# 16-BitSWStatusLed.net
KiCad netlist of a schematic drawn in Altium Designer
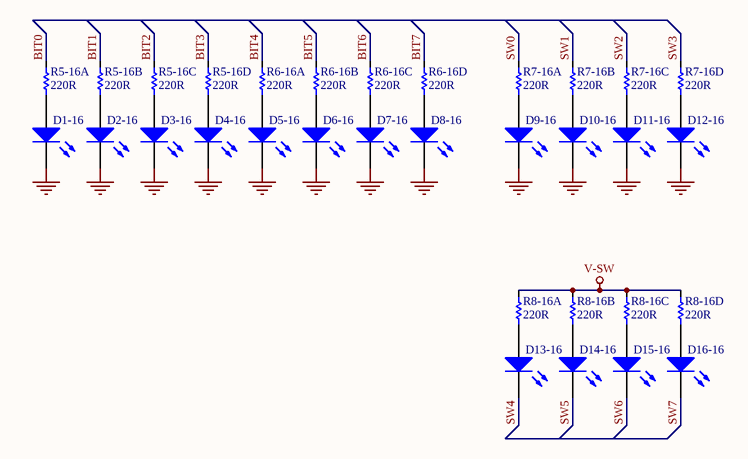
[diagram p0: 16-BitSWStatusLed.SchDoc]

(export (version "E")
  (design (tool "Eeschema 10.0.6"))
  (components
    (comp (ref "D1-16")
      (value "LED")
      (footprint "LED-0805")
      (description "Typical RED, GREEN, YELLOW, AMBER GaAs LED")
      (fields (field (name "PUBLISHER") "Altium Limited"))
      (libsource (lib "Miscellaneous Devices") (part "LED2"))
    )
    (comp (ref "D2-16")
      (value "LED")
      (footprint "LED-0805")
      (description "Typical RED, GREEN, YELLOW, AMBER GaAs LED")
      (fields (field (name "PUBLISHER") "Altium Limited"))
      (libsource (lib "Miscellaneous Devices") (part "LED2"))
    )
    (comp (ref "D3-16")
      (value "LED")
      (footprint "LED-0805")
      (description "Typical RED, GREEN, YELLOW, AMBER GaAs LED")
      (fields (field (name "PUBLISHER") "Altium Limited"))
      (libsource (lib "Miscellaneous Devices") (part "LED2"))
    )
    (comp (ref "D4-16")
      (value "LED")
      (footprint "LED-0805")
      (description "Typical RED, GREEN, YELLOW, AMBER GaAs LED")
      (fields (field (name "PUBLISHER") "Altium Limited"))
      (libsource (lib "Miscellaneous Devices") (part "LED2"))
    )
    (comp (ref "D5-16")
      (value "LED")
      (footprint "LED-0805")
      (description "Typical RED, GREEN, YELLOW, AMBER GaAs LED")
      (fields (field (name "PUBLISHER") "Altium Limited"))
      (libsource (lib "Miscellaneous Devices") (part "LED2"))
    )
    (comp (ref "D6-16")
      (value "LED")
      (footprint "LED-0805")
      (description "Typical RED, GREEN, YELLOW, AMBER GaAs LED")
      (fields (field (name "PUBLISHER") "Altium Limited"))
      (libsource (lib "Miscellaneous Devices") (part "LED2"))
    )
    (comp (ref "D7-16")
      (value "LED")
      (footprint "LED-0805")
      (description "Typical RED, GREEN, YELLOW, AMBER GaAs LED")
      (fields (field (name "PUBLISHER") "Altium Limited"))
      (libsource (lib "Miscellaneous Devices") (part "LED2"))
    )
    (comp (ref "D8-16")
      (value "LED")
      (footprint "LED-0805")
      (description "Typical RED, GREEN, YELLOW, AMBER GaAs LED")
      (fields (field (name "PUBLISHER") "Altium Limited"))
      (libsource (lib "Miscellaneous Devices") (part "LED2"))
    )
    (comp (ref "D9-16")
      (value "LED")
      (footprint "LED-0805")
      (description "Typical RED, GREEN, YELLOW, AMBER GaAs LED")
      (fields (field (name "PUBLISHER") "Altium Limited"))
      (libsource (lib "Miscellaneous Devices") (part "LED2"))
    )
    (comp (ref "D10-16")
      (value "LED")
      (footprint "LED-0805")
      (description "Typical RED, GREEN, YELLOW, AMBER GaAs LED")
      (fields (field (name "PUBLISHER") "Altium Limited"))
      (libsource (lib "Miscellaneous Devices") (part "LED2"))
    )
    (comp (ref "D11-16")
      (value "LED")
      (footprint "LED-0805")
      (description "Typical RED, GREEN, YELLOW, AMBER GaAs LED")
      (fields (field (name "PUBLISHER") "Altium Limited"))
      (libsource (lib "Miscellaneous Devices") (part "LED2"))
    )
    (comp (ref "D12-16")
      (value "LED")
      (footprint "LED-0805")
      (description "Typical RED, GREEN, YELLOW, AMBER GaAs LED")
      (fields (field (name "PUBLISHER") "Altium Limited"))
      (libsource (lib "Miscellaneous Devices") (part "LED2"))
    )
    (comp (ref "D13-16")
      (value "LED")
      (footprint "LED-0805")
      (description "Typical RED, GREEN, YELLOW, AMBER GaAs LED")
      (fields (field (name "PUBLISHER") "Altium Limited"))
      (libsource (lib "Miscellaneous Devices") (part "LED2"))
    )
    (comp (ref "D14-16")
      (value "LED")
      (footprint "LED-0805")
      (description "Typical RED, GREEN, YELLOW, AMBER GaAs LED")
      (fields (field (name "PUBLISHER") "Altium Limited"))
      (libsource (lib "Miscellaneous Devices") (part "LED2"))
    )
    (comp (ref "D15-16")
      (value "LED")
      (footprint "LED-0805")
      (description "Typical RED, GREEN, YELLOW, AMBER GaAs LED")
      (fields (field (name "PUBLISHER") "Altium Limited"))
      (libsource (lib "Miscellaneous Devices") (part "LED2"))
    )
    (comp (ref "D16-16")
      (value "LED")
      (footprint "LED-0805")
      (description "Typical RED, GREEN, YELLOW, AMBER GaAs LED")
      (fields (field (name "PUBLISHER") "Altium Limited"))
      (libsource (lib "Miscellaneous Devices") (part "LED2"))
    )
    (comp (ref "R5-16")
      (value "220R")
      (footprint "R-Array-0603-4")
      (description "RES ARRAY 4 RES 330 OHM 1206")
      (fields
        (field (name "DIGI-KEY PART NUMBER") "Y9331TR-ND")
        (field (name "MANUFACTURER") "Panasonic Electronic Components")
      )
      (libsource (lib "Dlib") (part "R-8P4R"))
    )
    (comp (ref "R6-16")
      (value "220R")
      (footprint "R-Array-0603-4")
      (description "RES ARRAY 4 RES 330 OHM 1206")
      (fields
        (field (name "DIGI-KEY PART NUMBER") "Y9331TR-ND")
        (field (name "MANUFACTURER") "Panasonic Electronic Components")
      )
      (libsource (lib "Dlib") (part "R-8P4R"))
    )
    (comp (ref "R7-16")
      (value "220R")
      (footprint "R-Array-0603-4")
      (description "RES ARRAY 4 RES 330 OHM 1206")
      (fields
        (field (name "DIGI-KEY PART NUMBER") "Y9331TR-ND")
        (field (name "MANUFACTURER") "Panasonic Electronic Components")
      )
      (libsource (lib "Dlib") (part "R-8P4R"))
    )
    (comp (ref "R8-16")
      (value "220R")
      (footprint "R-Array-0603-4")
      (description "RES ARRAY 4 RES 330 OHM 1206")
      (fields
        (field (name "DIGI-KEY PART NUMBER") "Y9331TR-ND")
        (field (name "MANUFACTURER") "Panasonic Electronic Components")
      )
      (libsource (lib "Dlib") (part "R-8P4R"))
    )
  )
  (nets
    (net (code "1") (name "/BIT0") (class "Default")
      (node (ref "R5-16") (pin "2") (pinfunction "2_2") (pintype "passive"))
    )
    (net (code "2") (name "/BIT1") (class "Default")
      (node (ref "R5-16") (pin "4") (pinfunction "2_4") (pintype "passive"))
    )
    (net (code "3") (name "/BIT2") (class "Default")
      (node (ref "R5-16") (pin "6") (pinfunction "2_6") (pintype "passive"))
    )
    (net (code "4") (name "/BIT3") (class "Default")
      (node (ref "R5-16") (pin "8") (pinfunction "2_8") (pintype "passive"))
    )
    (net (code "5") (name "/BIT4") (class "Default")
      (node (ref "R6-16") (pin "2") (pinfunction "2_2") (pintype "passive"))
    )
    (net (code "6") (name "/BIT5") (class "Default")
      (node (ref "R6-16") (pin "4") (pinfunction "2_4") (pintype "passive"))
    )
    (net (code "7") (name "/BIT6") (class "Default")
      (node (ref "R6-16") (pin "6") (pinfunction "2_6") (pintype "passive"))
    )
    (net (code "8") (name "/BIT7") (class "Default")
      (node (ref "R6-16") (pin "8") (pinfunction "2_8") (pintype "passive"))
    )
    (net (code "9") (name "/SW0") (class "Default")
      (node (ref "R7-16") (pin "2") (pinfunction "2_2") (pintype "passive"))
    )
    (net (code "10") (name "/SW1") (class "Default")
      (node (ref "R7-16") (pin "4") (pinfunction "2_4") (pintype "passive"))
    )
    (net (code "11") (name "/SW2") (class "Default")
      (node (ref "R7-16") (pin "6") (pinfunction "2_6") (pintype "passive"))
    )
    (net (code "12") (name "/SW3") (class "Default")
      (node (ref "R7-16") (pin "8") (pinfunction "2_8") (pintype "passive"))
    )
    (net (code "13") (name "/SW4") (class "Default")
      (node (ref "D13-16") (pin "2") (pinfunction "K_2") (pintype "passive"))
    )
    (net (code "14") (name "/SW5") (class "Default")
      (node (ref "D14-16") (pin "2") (pinfunction "K_2") (pintype "passive"))
    )
    (net (code "15") (name "/SW6") (class "Default")
      (node (ref "D15-16") (pin "2") (pinfunction "K_2") (pintype "passive"))
    )
    (net (code "16") (name "/SW7") (class "Default")
      (node (ref "D16-16") (pin "2") (pinfunction "K_2") (pintype "passive"))
    )
    (net (code "17") (name "GND") (class "Default")
      (node (ref "D1-16") (pin "2") (pinfunction "K_2") (pintype "passive"))
      (node (ref "D10-16") (pin "2") (pinfunction "K_2") (pintype "passive"))
      (node (ref "D11-16") (pin "2") (pinfunction "K_2") (pintype "passive"))
      (node (ref "D12-16") (pin "2") (pinfunction "K_2") (pintype "passive"))
      (node (ref "D2-16") (pin "2") (pinfunction "K_2") (pintype "passive"))
      (node (ref "D3-16") (pin "2") (pinfunction "K_2") (pintype "passive"))
      (node (ref "D4-16") (pin "2") (pinfunction "K_2") (pintype "passive"))
      (node (ref "D5-16") (pin "2") (pinfunction "K_2") (pintype "passive"))
      (node (ref "D6-16") (pin "2") (pinfunction "K_2") (pintype "passive"))
      (node (ref "D7-16") (pin "2") (pinfunction "K_2") (pintype "passive"))
      (node (ref "D8-16") (pin "2") (pinfunction "K_2") (pintype "passive"))
      (node (ref "D9-16") (pin "2") (pinfunction "K_2") (pintype "passive"))
    )
    (net (code "18") (name "Net-(D1-16-A)") (class "Default")
      (node (ref "D1-16") (pin "1") (pinfunction "A_1") (pintype "passive"))
      (node (ref "R5-16") (pin "1") (pinfunction "1_1") (pintype "passive"))
    )
    (net (code "19") (name "Net-(D2-16-A)") (class "Default")
      (node (ref "D2-16") (pin "1") (pinfunction "A_1") (pintype "passive"))
      (node (ref "R5-16") (pin "3") (pinfunction "1_3") (pintype "passive"))
    )
    (net (code "20") (name "Net-(D3-16-A)") (class "Default")
      (node (ref "D3-16") (pin "1") (pinfunction "A_1") (pintype "passive"))
      (node (ref "R5-16") (pin "5") (pinfunction "1_5") (pintype "passive"))
    )
    (net (code "21") (name "Net-(D4-16-A)") (class "Default")
      (node (ref "D4-16") (pin "1") (pinfunction "A_1") (pintype "passive"))
      (node (ref "R5-16") (pin "7") (pinfunction "1_7") (pintype "passive"))
    )
    (net (code "22") (name "Net-(D5-16-A)") (class "Default")
      (node (ref "D5-16") (pin "1") (pinfunction "A_1") (pintype "passive"))
      (node (ref "R6-16") (pin "1") (pinfunction "1_1") (pintype "passive"))
    )
    (net (code "23") (name "Net-(D6-16-A)") (class "Default")
      (node (ref "D6-16") (pin "1") (pinfunction "A_1") (pintype "passive"))
      (node (ref "R6-16") (pin "3") (pinfunction "1_3") (pintype "passive"))
    )
    (net (code "24") (name "Net-(D7-16-A)") (class "Default")
      (node (ref "D7-16") (pin "1") (pinfunction "A_1") (pintype "passive"))
      (node (ref "R6-16") (pin "5") (pinfunction "1_5") (pintype "passive"))
    )
    (net (code "25") (name "Net-(D8-16-A)") (class "Default")
      (node (ref "D8-16") (pin "1") (pinfunction "A_1") (pintype "passive"))
      (node (ref "R6-16") (pin "7") (pinfunction "1_7") (pintype "passive"))
    )
    (net (code "26") (name "Net-(D9-16-A)") (class "Default")
      (node (ref "D9-16") (pin "1") (pinfunction "A_1") (pintype "passive"))
      (node (ref "R7-16") (pin "1") (pinfunction "1_1") (pintype "passive"))
    )
    (net (code "27") (name "Net-(D10-16-A)") (class "Default")
      (node (ref "D10-16") (pin "1") (pinfunction "A_1") (pintype "passive"))
      (node (ref "R7-16") (pin "3") (pinfunction "1_3") (pintype "passive"))
    )
    (net (code "28") (name "Net-(D11-16-A)") (class "Default")
      (node (ref "D11-16") (pin "1") (pinfunction "A_1") (pintype "passive"))
      (node (ref "R7-16") (pin "5") (pinfunction "1_5") (pintype "passive"))
    )
    (net (code "29") (name "Net-(D12-16-A)") (class "Default")
      (node (ref "D12-16") (pin "1") (pinfunction "A_1") (pintype "passive"))
      (node (ref "R7-16") (pin "7") (pinfunction "1_7") (pintype "passive"))
    )
    (net (code "30") (name "Net-(D13-16-A)") (class "Default")
      (node (ref "D13-16") (pin "1") (pinfunction "A_1") (pintype "passive"))
      (node (ref "R8-16") (pin "1") (pinfunction "1_1") (pintype "passive"))
    )
    (net (code "31") (name "Net-(D14-16-A)") (class "Default")
      (node (ref "D14-16") (pin "1") (pinfunction "A_1") (pintype "passive"))
      (node (ref "R8-16") (pin "3") (pinfunction "1_3") (pintype "passive"))
    )
    (net (code "32") (name "Net-(D15-16-A)") (class "Default")
      (node (ref "D15-16") (pin "1") (pinfunction "A_1") (pintype "passive"))
      (node (ref "R8-16") (pin "5") (pinfunction "1_5") (pintype "passive"))
    )
    (net (code "33") (name "Net-(D16-16-A)") (class "Default")
      (node (ref "D16-16") (pin "1") (pinfunction "A_1") (pintype "passive"))
      (node (ref "R8-16") (pin "7") (pinfunction "1_7") (pintype "passive"))
    )
    (net (code "34") (name "V-SW") (class "Default")
      (node (ref "R8-16") (pin "2") (pinfunction "2_2") (pintype "passive"))
      (node (ref "R8-16") (pin "4") (pinfunction "2_4") (pintype "passive"))
      (node (ref "R8-16") (pin "6") (pinfunction "2_6") (pintype "passive"))
      (node (ref "R8-16") (pin "8") (pinfunction "2_8") (pintype "passive"))
    )
  )
)
